# openSX70_MEROE_V7-5_20190606-TCS3200.net
KiCad netlist of a schematic drawn in EAGLE
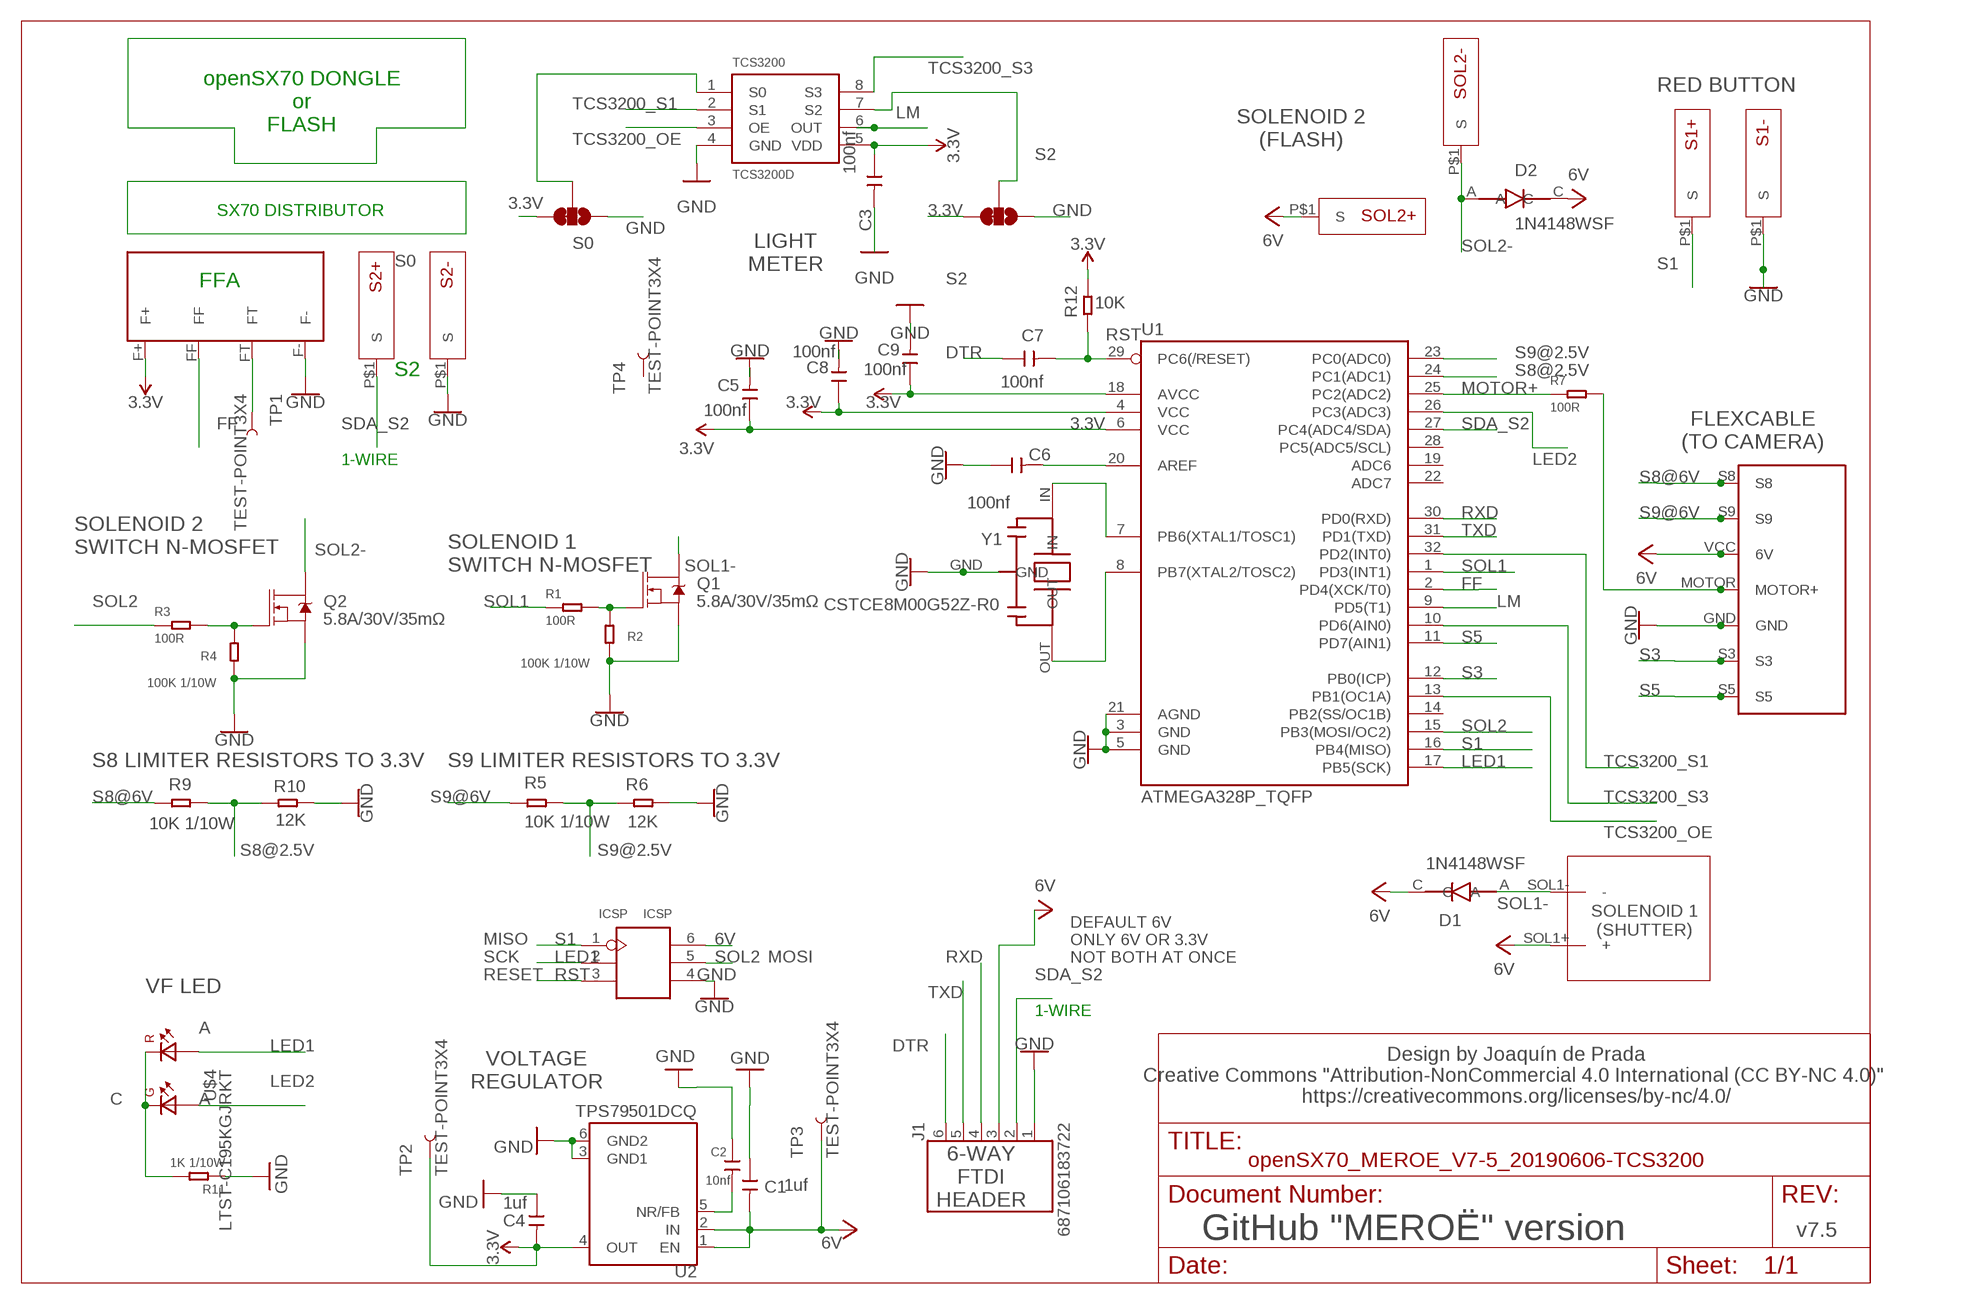
[diagram p0: schematic, sheet 1]

(export (version "E")
  (design (tool "Eeschema 10.0.6"))
  (components
    (comp (ref "C1")
      (value "1uf")
      (footprint "eagle-import:C0603")
      (fields (field (name "MPN") "CC0603KRX5R6BB106"))
      (libsource (lib "eagle-import") (part "CERAMIC-10UF-10V-10%-X5R(0603)"))
    )
    (comp (ref "C2")
      (value "10nf")
      (footprint "eagle-import:C0603")
      (fields (field (name "MPN") "CC0603KRX7R9BB104"))
      (libsource (lib "eagle-import") (part "CERAMIC-100NF-50V-10%-X7R(0603)"))
    )
    (comp (ref "C3")
      (value "100nf")
      (footprint "eagle-import:C0603")
      (fields (field (name "MPN") "CC0603KRX7R9BB104"))
      (libsource (lib "eagle-import") (part "CERAMIC-100NF-50V-10%-X7R(0603)"))
    )
    (comp (ref "C4")
      (value "1uf")
      (footprint "eagle-import:C0603")
      (fields (field (name "MPN") "CC0603KRX5R6BB106"))
      (libsource (lib "eagle-import") (part "CERAMIC-10UF-10V-10%-X5R(0603)"))
    )
    (comp (ref "C5")
      (value "100nf")
      (footprint "eagle-import:C0603")
      (fields (field (name "MPN") "CC0603KRX7R9BB104"))
      (libsource (lib "eagle-import") (part "CERAMIC-100NF-50V-10%-X7R(0603)"))
    )
    (comp (ref "C6")
      (value "100nf")
      (footprint "eagle-import:C0603")
      (fields (field (name "MPN") "CC0603KRX7R9BB104"))
      (libsource (lib "eagle-import") (part "CERAMIC-100NF-50V-10%-X7R(0603)"))
    )
    (comp (ref "C7")
      (value "100nf")
      (footprint "eagle-import:C0603")
      (fields (field (name "MPN") "CC0603KRX7R9BB104"))
      (libsource (lib "eagle-import") (part "CERAMIC-100NF-50V-10%-X7R(0603)"))
    )
    (comp (ref "C8")
      (value "100nf")
      (footprint "eagle-import:C0603")
      (fields (field (name "MPN") "CC0603KRX7R9BB104"))
      (libsource (lib "eagle-import") (part "CERAMIC-100NF-50V-10%-X7R(0603)"))
    )
    (comp (ref "C9")
      (value "100nf")
      (footprint "eagle-import:C0603")
      (fields (field (name "MPN") "CC0603KRX7R9BB104"))
      (libsource (lib "eagle-import") (part "CERAMIC-100NF-50V-10%-X7R(0603)"))
    )
    (comp (ref "D1")
      (value "1N4148WSF")
      (footprint "eagle-import:SODFL2512X100N")
      (fields (field (name "MANUFACTURER") "Fairchild Semiconductor"))
      (libsource (lib "eagle-import") (part "1N4148WS"))
    )
    (comp (ref "D2")
      (value "1N4148WSF")
      (footprint "eagle-import:SODFL2512X100N")
      (fields (field (name "MANUFACTURER") "Fairchild Semiconductor"))
      (libsource (lib "eagle-import") (part "1N4148WS"))
    )
    (comp (ref "ICSP")
      (value "ICSP")
      (footprint "eagle-import:H2X3-2.54")
      (libsource (lib "eagle-import") (part "ICSP"))
    )
    (comp (ref "J1")
      (value "687106183722")
      (footprint "eagle-import:687106183722")
      (fields (field (name "MF") "Wurth Electronics"))
      (libsource (lib "eagle-import") (part "687106183722"))
    )
    (comp (ref "Q1")
      (value "5.8A/30V/35mΩ")
      (footprint "eagle-import:SOT23-3")
      (libsource (lib "eagle-import") (part "MOSFET-NCH-AO3404A"))
    )
    (comp (ref "Q2")
      (value "5.8A/30V/35mΩ")
      (footprint "eagle-import:SOT23-3")
      (libsource (lib "eagle-import") (part "MOSFET-NCH-AO3404A"))
    )
    (comp (ref "R1")
      (value "100R")
      (footprint "eagle-import:R0603")
      (fields (field (name "MPN") "RC0603JR-07100RL"))
      (libsource (lib "eagle-import") (part "SMD-RES-100R-5%-1/10W(0603)"))
    )
    (comp (ref "R2")
      (value "100K 1/10W")
      (footprint "eagle-import:R0603")
      (fields (field (name "MPN") "RC0603JR-07100KL"))
      (libsource (lib "eagle-import") (part "SMD-RES-100K-5%-1/10W(0603)"))
    )
    (comp (ref "R3")
      (value "100R")
      (footprint "eagle-import:R0603")
      (fields (field (name "MPN") "RC0603JR-07100RL"))
      (libsource (lib "eagle-import") (part "SMD-RES-100R-5%-1/10W(0603)"))
    )
    (comp (ref "R4")
      (value "100K 1/10W")
      (footprint "eagle-import:R0603")
      (fields (field (name "MPN") "RC0603JR-07100KL"))
      (libsource (lib "eagle-import") (part "SMD-RES-100K-5%-1/10W(0603)"))
    )
    (comp (ref "R5")
      (value "10K 1/10W")
      (footprint "eagle-import:R0603")
      (fields (field (name "MPN") "RC0603FR-0715KL"))
      (libsource (lib "eagle-import") (part "SMD-RES-15K-1%-1/10W(0603)"))
    )
    (comp (ref "R6")
      (value "12K")
      (footprint "eagle-import:R0603")
      (fields (field (name "MPN") "RC0603FR-0710KL"))
      (libsource (lib "eagle-import") (part "SMD-RES-10K-1%-1/10W(0603)"))
    )
    (comp (ref "R7")
      (value "100R")
      (footprint "eagle-import:R0603")
      (fields (field (name "MPN") "RC0603JR-07100RL"))
      (libsource (lib "eagle-import") (part "SMD-RES-100R-5%-1/10W(0603)"))
    )
    (comp (ref "R9")
      (value "10K 1/10W")
      (footprint "eagle-import:R0603")
      (fields (field (name "MPN") "RC0603FR-0715KL"))
      (libsource (lib "eagle-import") (part "SMD-RES-15K-1%-1/10W(0603)"))
    )
    (comp (ref "R10")
      (value "12K")
      (footprint "eagle-import:R0603")
      (fields (field (name "MPN") "RC0603FR-0710KL"))
      (libsource (lib "eagle-import") (part "SMD-RES-10K-1%-1/10W(0603)"))
    )
    (comp (ref "R11")
      (value "1K 1/10W")
      (footprint "eagle-import:R0603")
      (fields (field (name "MPN") "RC0603JR-071KL"))
      (libsource (lib "eagle-import") (part "SMD-RES-1K-5%-1/10W(0603)"))
    )
    (comp (ref "R12")
      (value "10K")
      (footprint "eagle-import:R0603")
      (fields (field (name "MPN") "RC0603FR-0710KL"))
      (libsource (lib "eagle-import") (part "SMD-RES-10K-1%-1/10W(0603)"))
    )
    (comp (ref "S0")
      (value "S0")
      (footprint "eagle-import:SMT-JUMPER_3_1-NC_TRACE_SILK")
      (libsource (lib "eagle-import") (part "JUMPER-SMT_3_1-NC_TRACE_SILK"))
    )
    (comp (ref "S1+")
      (value "SX70-S-PAD-NEW")
      (footprint "eagle-import:SX70-S-PAD2")
      (libsource (lib "eagle-import") (part "SX70-S-PAD-NEW"))
    )
    (comp (ref "S1-")
      (value "SX70-S-PAD-NEW")
      (footprint "eagle-import:SX70-S-PAD2")
      (libsource (lib "eagle-import") (part "SX70-S-PAD-NEW"))
    )
    (comp (ref "S2")
      (value "S2")
      (footprint "eagle-import:SMT-JUMPER_3_1-NC_TRACE_SILK")
      (libsource (lib "eagle-import") (part "JUMPER-SMT_3_1-NC_TRACE_SILK"))
    )
    (comp (ref "S2+")
      (value "SX70-S-PAD-NEW")
      (footprint "eagle-import:SX70-S-PAD2")
      (libsource (lib "eagle-import") (part "SX70-S-PAD-NEW"))
    )
    (comp (ref "S2-")
      (value "SX70-S-PAD-NEW")
      (footprint "eagle-import:SX70-S-PAD2")
      (libsource (lib "eagle-import") (part "SX70-S-PAD-NEW"))
    )
    (comp (ref "SOL1")
      (value "SX70-SOLENOID1-2PADS")
      (footprint "eagle-import:SX70-SOLENOID1-2")
      (libsource (lib "eagle-import") (part "SX70-SOLENOID1-2PADS"))
    )
    (comp (ref "SOL2+")
      (value "SX70-S-PAD-NEW")
      (footprint "eagle-import:SX70-S-PAD2")
      (libsource (lib "eagle-import") (part "SX70-S-PAD-NEW"))
    )
    (comp (ref "SOL2-")
      (value "SX70-S-PAD-NEW")
      (footprint "eagle-import:SX70-S-PAD2")
      (libsource (lib "eagle-import") (part "SX70-S-PAD-NEW"))
    )
    (comp (ref "TCS3200")
      (value "TCS3200D")
      (footprint "eagle-import:SOIC8")
      (fields (field (name "MF") "ams") (field (name "MP") "TCS3200D-TR"))
      (libsource (lib "eagle-import") (part "TCS3200D"))
    )
    (comp (ref "TP1")
      (value "TEST-POINT3X4")
      (footprint "eagle-import:PAD.03X.04")
      (libsource (lib "eagle-import") (part "TEST-POINT3X4"))
    )
    (comp (ref "TP2")
      (value "TEST-POINT3X4")
      (footprint "eagle-import:PAD.03X.04")
      (libsource (lib "eagle-import") (part "TEST-POINT3X4"))
    )
    (comp (ref "TP3")
      (value "TEST-POINT3X4")
      (footprint "eagle-import:PAD.03X.04")
      (libsource (lib "eagle-import") (part "TEST-POINT3X4"))
    )
    (comp (ref "TP4")
      (value "TEST-POINT3X4")
      (footprint "eagle-import:PAD.03X.04")
      (libsource (lib "eagle-import") (part "TEST-POINT3X4"))
    )
    (comp (ref "U$1")
      (value "SX70-7-PAD")
      (footprint "eagle-import:SX70-7-PAD-PROPER")
      (libsource (lib "eagle-import") (part "SX70-7-PAD"))
    )
    (comp (ref "U$2")
      (value "FFA")
      (footprint "eagle-import:FFA-PAD-PACKAGE")
      (libsource (lib "eagle-import") (part "SX70-FFA-PAD"))
    )
    (comp (ref "U$4")
      (value "LTST-C195KGJRKT")
      (footprint "eagle-import:LTST-BILED-15X16")
      (fields (field (name "MF") "Lite-On Inc."))
      (libsource (lib "eagle-import") (part "LTST-C195KGJRKT"))
    )
    (comp (ref "U1")
      (value "ATMEGA328P_TQFP")
      (footprint "eagle-import:TQFP32-08")
      (libsource (lib "eagle-import") (part "ATMEGA328P_TQFP"))
    )
    (comp (ref "U2")
      (value "TPS79501DCQ")
      (footprint "eagle-import:SOT127P706X180-6N")
      (fields (field (name "MF") "Texas Instruments"))
      (libsource (lib "eagle-import") (part "TPS79501DCQ"))
    )
    (comp (ref "Y1")
      (value "CSTCE8M00G52Z-R0")
      (footprint "eagle-import:CFP95P160X100-3N")
      (fields (field (name "MF") "Murata") (field (name "MP") "CSTCE16M0V53-R0"))
      (libsource (lib "eagle-import") (part "CSTCE16M0V53-R0"))
    )
  )
  (nets
    (net (code "1") (name "/DTR") (class "Default")
      (node (ref "C7") (pin "1") (pinfunction "1_1") (pintype "passive"))
      (node (ref "J1") (pin "6") (pinfunction "1_6") (pintype "passive"))
    )
    (net (code "2") (name "/FF") (class "Default")
      (node (ref "U$2") (pin "FF") (pinfunction "FF_FF") (pintype "bidirectional"))
      (node (ref "U1") (pin "2") (pinfunction "PD4(XCK/T0)_2") (pintype "bidirectional"))
    )
    (net (code "3") (name "/LED1") (class "Default")
      (node (ref "ICSP") (pin "2") (pinfunction "SCK_2") (pintype "bidirectional"))
      (node (ref "U$4") (pin "P$2") (pinfunction "A2_P$2") (pintype "passive"))
      (node (ref "U1") (pin "17") (pinfunction "PB5(SCK)_17") (pintype "bidirectional"))
    )
    (net (code "4") (name "/LED2") (class "Default")
      (node (ref "U$4") (pin "P$1") (pinfunction "A1_P$1") (pintype "passive"))
      (node (ref "U1") (pin "26") (pinfunction "PC3(ADC3)_26") (pintype "bidirectional"))
    )
    (net (code "5") (name "/LM") (class "Default")
      (node (ref "TCS3200") (pin "6") (pinfunction "OUT_6") (pintype "bidirectional"))
      (node (ref "U1") (pin "9") (pinfunction "PD5(T1)_9") (pintype "bidirectional"))
    )
    (net (code "6") (name "/MOTOR+") (class "Default")
      (node (ref "R7") (pin "1") (pinfunction "1_1") (pintype "passive"))
      (node (ref "U1") (pin "25") (pinfunction "PC2(ADC2)_25") (pintype "bidirectional"))
    )
    (net (code "7") (name "/RST") (class "Default")
      (node (ref "C7") (pin "2") (pinfunction "2_2") (pintype "passive"))
      (node (ref "ICSP") (pin "3") (pinfunction "RST_3") (pintype "bidirectional"))
      (node (ref "R12") (pin "1") (pinfunction "1_1") (pintype "passive"))
      (node (ref "U1") (pin "29") (pinfunction "PC6(/RESET)_29") (pintype "bidirectional"))
    )
    (net (code "8") (name "/RXD") (class "Default")
      (node (ref "J1") (pin "4") (pinfunction "3_4") (pintype "passive"))
      (node (ref "U1") (pin "30") (pinfunction "PD0(RXD)_30") (pintype "bidirectional"))
    )
    (net (code "9") (name "/S1") (class "Default")
      (node (ref "ICSP") (pin "1") (pinfunction "MISO_1") (pintype "bidirectional"))
      (node (ref "S1+") (pin "P$1") (pinfunction "S_P$1") (pintype "bidirectional"))
      (node (ref "U1") (pin "16") (pinfunction "PB4(MISO)_16") (pintype "bidirectional"))
    )
    (net (code "10") (name "/S3") (class "Default")
      (node (ref "U$1") (pin "S3") (pinfunction "S3_S3") (pintype "bidirectional"))
      (node (ref "U1") (pin "12") (pinfunction "PB0(ICP)_12") (pintype "bidirectional"))
    )
    (net (code "11") (name "/S5") (class "Default")
      (node (ref "U$1") (pin "S5") (pinfunction "S5_S5") (pintype "bidirectional"))
      (node (ref "U1") (pin "11") (pinfunction "PD7(AIN1)_11") (pintype "bidirectional"))
    )
    (net (code "12") (name "/S8@2.5V") (class "Default")
      (node (ref "R10") (pin "1") (pinfunction "1_1") (pintype "passive"))
      (node (ref "R9") (pin "2") (pinfunction "2_2") (pintype "passive"))
      (node (ref "U1") (pin "24") (pinfunction "PC1(ADC1)_24") (pintype "bidirectional"))
    )
    (net (code "13") (name "/S8@6V") (class "Default")
      (node (ref "R9") (pin "1") (pinfunction "1_1") (pintype "passive"))
      (node (ref "U$1") (pin "S8") (pinfunction "S8_S8") (pintype "bidirectional"))
    )
    (net (code "14") (name "/S9@2.5V") (class "Default")
      (node (ref "R5") (pin "2") (pinfunction "2_2") (pintype "passive"))
      (node (ref "R6") (pin "1") (pinfunction "1_1") (pintype "passive"))
      (node (ref "U1") (pin "23") (pinfunction "PC0(ADC0)_23") (pintype "bidirectional"))
    )
    (net (code "15") (name "/S9@6V") (class "Default")
      (node (ref "R5") (pin "1") (pinfunction "1_1") (pintype "passive"))
      (node (ref "U$1") (pin "S9") (pinfunction "S9_S9") (pintype "bidirectional"))
    )
    (net (code "16") (name "/SDA_S2") (class "Default")
      (node (ref "J1") (pin "2") (pinfunction "5_2") (pintype "passive"))
      (node (ref "S2+") (pin "P$1") (pinfunction "S_P$1") (pintype "bidirectional"))
      (node (ref "U1") (pin "27") (pinfunction "PC4(ADC4/SDA)_27") (pintype "bidirectional"))
    )
    (net (code "17") (name "/SOL1") (class "Default")
      (node (ref "R1") (pin "1") (pinfunction "1_1") (pintype "passive"))
      (node (ref "U1") (pin "1") (pinfunction "PD3(INT1)_1") (pintype "bidirectional"))
    )
    (net (code "18") (name "/SOL1-") (class "Default")
      (node (ref "D1") (pin "A") (pinfunction "A_A") (pintype "passive"))
      (node (ref "Q1") (pin "3") (pinfunction "D_3") (pintype "bidirectional"))
      (node (ref "SOL1") (pin "SOL1-") (pinfunction "-_SOL1-") (pintype "bidirectional"))
    )
    (net (code "19") (name "/SOL2") (class "Default")
      (node (ref "ICSP") (pin "5") (pinfunction "MOSI_5") (pintype "bidirectional"))
      (node (ref "R3") (pin "1") (pinfunction "1_1") (pintype "passive"))
      (node (ref "U1") (pin "15") (pinfunction "PB3(MOSI/OC2)_15") (pintype "bidirectional"))
    )
    (net (code "20") (name "/SOL2-") (class "Default")
      (node (ref "D2") (pin "A") (pinfunction "A_A") (pintype "passive"))
      (node (ref "Q2") (pin "3") (pinfunction "D_3") (pintype "bidirectional"))
      (node (ref "SOL2-") (pin "P$1") (pinfunction "S_P$1") (pintype "bidirectional"))
    )
    (net (code "21") (name "/TCS3200_OE") (class "Default")
      (node (ref "TCS3200") (pin "3") (pinfunction "OE_3") (pintype "bidirectional"))
      (node (ref "U1") (pin "13") (pinfunction "PB1(OC1A)_13") (pintype "bidirectional"))
    )
    (net (code "22") (name "/TCS3200_S1") (class "Default")
      (node (ref "TCS3200") (pin "2") (pinfunction "S1_2") (pintype "bidirectional"))
      (node (ref "U1") (pin "32") (pinfunction "PD2(INT0)_32") (pintype "bidirectional"))
    )
    (net (code "23") (name "/TCS3200_S3") (class "Default")
      (node (ref "TCS3200") (pin "8") (pinfunction "S3_8") (pintype "bidirectional"))
      (node (ref "U1") (pin "10") (pinfunction "PD6(AIN0)_10") (pintype "bidirectional"))
    )
    (net (code "24") (name "/TXD") (class "Default")
      (node (ref "J1") (pin "5") (pinfunction "2_5") (pintype "passive"))
      (node (ref "U1") (pin "31") (pinfunction "PD1(TXD)_31") (pintype "bidirectional"))
    )
    (net (code "25") (name "3.3V") (class "Default")
      (node (ref "C3") (pin "1") (pinfunction "1_1") (pintype "passive"))
      (node (ref "C4") (pin "2") (pinfunction "2_2") (pintype "passive"))
      (node (ref "C5") (pin "1") (pinfunction "1_1") (pintype "passive"))
      (node (ref "C8") (pin "1") (pinfunction "1_1") (pintype "passive"))
      (node (ref "C9") (pin "1") (pinfunction "1_1") (pintype "passive"))
      (node (ref "R12") (pin "2") (pinfunction "2_2") (pintype "passive"))
      (node (ref "S0") (pin "3") (pinfunction "3_3") (pintype "passive"))
      (node (ref "S2") (pin "3") (pinfunction "3_3") (pintype "passive"))
      (node (ref "TCS3200") (pin "5") (pinfunction "VDD_5") (pintype "bidirectional"))
      (node (ref "TP2") (pin "P$1") (pinfunction "1_P$1") (pintype "bidirectional"))
      (node (ref "U$2") (pin "F+") (pinfunction "F+_F+") (pintype "bidirectional"))
      (node (ref "U1") (pin "18") (pinfunction "AVCC_18") (pintype "bidirectional"))
      (node (ref "U1") (pin "4") (pinfunction "VCC_4") (pintype "bidirectional"))
      (node (ref "U1") (pin "6") (pinfunction "VCC_6") (pintype "bidirectional"))
      (node (ref "U2") (pin "4") (pinfunction "OUT_4") (pintype "output"))
    )
    (net (code "26") (name "6V") (class "Default")
      (node (ref "C1") (pin "2") (pinfunction "2_2") (pintype "passive"))
      (node (ref "D1") (pin "C") (pinfunction "C_C") (pintype "passive"))
      (node (ref "D2") (pin "C") (pinfunction "C_C") (pintype "passive"))
      (node (ref "ICSP") (pin "6") (pinfunction "VCC_6") (pintype "bidirectional"))
      (node (ref "J1") (pin "3") (pinfunction "4_3") (pintype "passive"))
      (node (ref "SOL1") (pin "SOL1+") (pinfunction "+_SOL1+") (pintype "bidirectional"))
      (node (ref "SOL2+") (pin "P$1") (pinfunction "S_P$1") (pintype "bidirectional"))
      (node (ref "TP3") (pin "P$1") (pinfunction "1_P$1") (pintype "bidirectional"))
      (node (ref "U$1") (pin "VCC") (pinfunction "6V_VCC") (pintype "bidirectional"))
      (node (ref "U2") (pin "1") (pinfunction "EN_1") (pintype "input"))
      (node (ref "U2") (pin "2") (pinfunction "IN_2") (pintype "input"))
    )
    (net (code "27") (name "GND") (class "Default")
      (node (ref "C1") (pin "1") (pinfunction "1_1") (pintype "passive"))
      (node (ref "C2") (pin "1") (pinfunction "1_1") (pintype "passive"))
      (node (ref "C3") (pin "2") (pinfunction "2_2") (pintype "passive"))
      (node (ref "C4") (pin "1") (pinfunction "1_1") (pintype "passive"))
      (node (ref "C5") (pin "2") (pinfunction "2_2") (pintype "passive"))
      (node (ref "C6") (pin "1") (pinfunction "1_1") (pintype "passive"))
      (node (ref "C8") (pin "2") (pinfunction "2_2") (pintype "passive"))
      (node (ref "C9") (pin "2") (pinfunction "2_2") (pintype "passive"))
      (node (ref "ICSP") (pin "4") (pinfunction "GND_4") (pintype "bidirectional"))
      (node (ref "J1") (pin "1") (pinfunction "6_1") (pintype "passive"))
      (node (ref "Q1") (pin "2") (pinfunction "S_2") (pintype "bidirectional"))
      (node (ref "Q2") (pin "2") (pinfunction "S_2") (pintype "bidirectional"))
      (node (ref "R10") (pin "2") (pinfunction "2_2") (pintype "passive"))
      (node (ref "R11") (pin "1") (pinfunction "1_1") (pintype "passive"))
      (node (ref "R2") (pin "1") (pinfunction "1_1") (pintype "passive"))
      (node (ref "R4") (pin "1") (pinfunction "1_1") (pintype "passive"))
      (node (ref "R6") (pin "2") (pinfunction "2_2") (pintype "passive"))
      (node (ref "S0") (pin "1") (pinfunction "1_1") (pintype "passive"))
      (node (ref "S1-") (pin "P$1") (pinfunction "S_P$1") (pintype "bidirectional"))
      (node (ref "S2") (pin "1") (pinfunction "1_1") (pintype "passive"))
      (node (ref "S2-") (pin "P$1") (pinfunction "S_P$1") (pintype "bidirectional"))
      (node (ref "TCS3200") (pin "4") (pinfunction "GND_4") (pintype "bidirectional"))
      (node (ref "U$1") (pin "GND") (pinfunction "GND_GND") (pintype "bidirectional"))
      (node (ref "U$2") (pin "F-") (pinfunction "F-_F-") (pintype "bidirectional"))
      (node (ref "U1") (pin "21") (pinfunction "AGND_21") (pintype "bidirectional"))
      (node (ref "U1") (pin "3") (pinfunction "GND_3") (pintype "bidirectional"))
      (node (ref "U1") (pin "5") (pinfunction "GND_5") (pintype "bidirectional"))
      (node (ref "U2") (pin "3") (pinfunction "GND1_3") (pintype "power_in"))
      (node (ref "U2") (pin "6") (pinfunction "GND2_6") (pintype "power_in"))
      (node (ref "Y1") (pin "GND") (pinfunction "GND_GND") (pintype "passive"))
    )
    (net (code "28") (name "Net-(Q1-G)") (class "Default")
      (node (ref "Q1") (pin "1") (pinfunction "G_1") (pintype "bidirectional"))
      (node (ref "R1") (pin "2") (pinfunction "2_2") (pintype "passive"))
      (node (ref "R2") (pin "2") (pinfunction "2_2") (pintype "passive"))
    )
    (net (code "29") (name "Net-(Q2-G)") (class "Default")
      (node (ref "Q2") (pin "1") (pinfunction "G_1") (pintype "bidirectional"))
      (node (ref "R3") (pin "2") (pinfunction "2_2") (pintype "passive"))
      (node (ref "R4") (pin "2") (pinfunction "2_2") (pintype "passive"))
    )
    (net (code "30") (name "Net-(TCS3200-S0)") (class "Default")
      (node (ref "S0") (pin "2") (pinfunction "2_2") (pintype "passive"))
      (node (ref "TCS3200") (pin "1") (pinfunction "S0_1") (pintype "bidirectional"))
    )
    (net (code "31") (name "Net-(TCS3200-S2)") (class "Default")
      (node (ref "S2") (pin "2") (pinfunction "2_2") (pintype "passive"))
      (node (ref "TCS3200") (pin "7") (pinfunction "S2_7") (pintype "bidirectional"))
    )
    (net (code "32") (name "Net-(TP1-1)") (class "Default")
      (node (ref "TP1") (pin "P$1") (pinfunction "1_P$1") (pintype "bidirectional"))
      (node (ref "U$2") (pin "FT") (pinfunction "FT_FT") (pintype "bidirectional"))
    )
    (net (code "33") (name "Net-(U$1-MOTOR+)") (class "Default")
      (node (ref "R7") (pin "2") (pinfunction "2_2") (pintype "passive"))
      (node (ref "U$1") (pin "MOTOR") (pinfunction "MOTOR+_MOTOR") (pintype "bidirectional"))
    )
    (net (code "34") (name "Net-(U$4-K1)") (class "Default")
      (node (ref "R11") (pin "2") (pinfunction "2_2") (pintype "passive"))
      (node (ref "U$4") (pin "P$3") (pinfunction "K1_P$3") (pintype "passive"))
      (node (ref "U$4") (pin "P$4") (pinfunction "K2_P$4") (pintype "passive"))
    )
    (net (code "35") (name "Net-(U1-AREF)") (class "Default")
      (node (ref "C6") (pin "2") (pinfunction "2_2") (pintype "passive"))
      (node (ref "U1") (pin "20") (pinfunction "AREF_20") (pintype "bidirectional"))
    )
    (net (code "36") (name "Net-(U1-PB6(XTAL1{slash}TOSC1))") (class "Default")
      (node (ref "U1") (pin "7") (pinfunction "PB6(XTAL1/TOSC1)_7") (pintype "bidirectional"))
      (node (ref "Y1") (pin "IN") (pinfunction "IN_IN") (pintype "input"))
    )
    (net (code "37") (name "Net-(U1-PB7(XTAL2{slash}TOSC2))") (class "Default")
      (node (ref "U1") (pin "8") (pinfunction "PB7(XTAL2/TOSC2)_8") (pintype "bidirectional"))
      (node (ref "Y1") (pin "OUT") (pinfunction "OUT_OUT") (pintype "output"))
    )
    (net (code "38") (name "Net-(U2-NR{slash}FB)") (class "Default")
      (node (ref "C2") (pin "2") (pinfunction "2_2") (pintype "passive"))
      (node (ref "U2") (pin "5") (pinfunction "NR/FB_5") (pintype "input"))
    )
    (net (code "39") (name "unconnected-(TP4-1-PadP$1)") (class "Default")
      (node (ref "TP4") (pin "P$1") (pinfunction "1_P$1") (pintype "bidirectional"))
    )
    (net (code "40") (name "unconnected-(U1-ADC6-Pad19)") (class "Default")
      (node (ref "U1") (pin "19") (pinfunction "ADC6_19") (pintype "bidirectional"))
    )
    (net (code "41") (name "unconnected-(U1-ADC7-Pad22)") (class "Default")
      (node (ref "U1") (pin "22") (pinfunction "ADC7_22") (pintype "bidirectional"))
    )
    (net (code "42") (name "unconnected-(U1-PB2(SS{slash}OC1B)-Pad14)") (class "Default")
      (node (ref "U1") (pin "14") (pinfunction "PB2(SS/OC1B)_14") (pintype "bidirectional"))
    )
    (net (code "43") (name "unconnected-(U1-PC5(ADC5{slash}SCL)-Pad28)") (class "Default")
      (node (ref "U1") (pin "28") (pinfunction "PC5(ADC5/SCL)_28") (pintype "bidirectional"))
    )
  )
)
